# CH3.net
KiCad netlist of a schematic drawn in Altium Designer
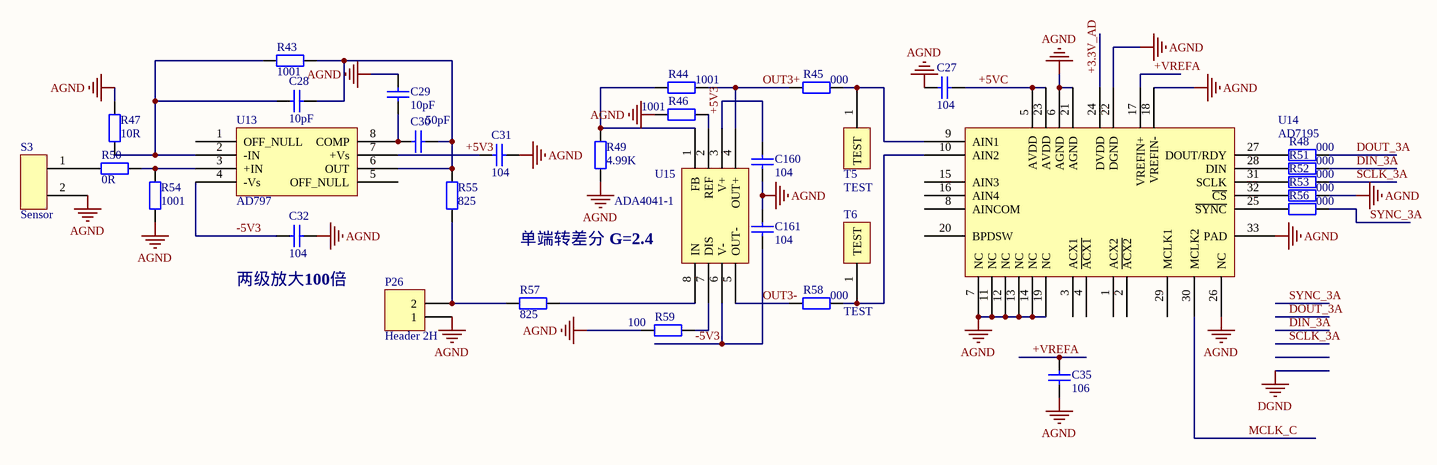
[diagram p0: CH3.SchDoc]

(export (version "E")
  (design (tool "Eeschema 10.0.6"))
  (components
    (comp (ref "C27")
      (value "104")
      (footprint "0805C")
      (description "Capacitor")
      (fields (field (name "PUBLISHER") "Altium Limited"))
      (libsource (lib "Miscellaneous Devices") (part "Cap"))
    )
    (comp (ref "C28")
      (value "10pF")
      (footprint "0603")
      (description "Capacitor")
      (fields (field (name "PUBLISHER") "Altium Limited"))
      (libsource (lib "Miscellaneous Devices") (part "Cap"))
    )
    (comp (ref "C29")
      (value "10pF")
      (footprint "0603")
      (description "Capacitor")
      (fields (field (name "PUBLISHER") "Altium Limited"))
      (libsource (lib "Miscellaneous Devices") (part "Cap"))
    )
    (comp (ref "C30")
      (value "50pF")
      (footprint "0603")
      (description "Capacitor")
      (fields (field (name "PUBLISHER") "Altium Limited"))
      (libsource (lib "Miscellaneous Devices") (part "Cap"))
    )
    (comp (ref "C31")
      (value "104")
      (footprint "0805C")
      (description "Capacitor")
      (fields (field (name "PUBLISHER") "Altium Limited"))
      (libsource (lib "Miscellaneous Devices") (part "Cap"))
    )
    (comp (ref "C32")
      (value "104")
      (footprint "0805C")
      (description "Capacitor")
      (fields (field (name "PUBLISHER") "Altium Limited"))
      (libsource (lib "Miscellaneous Devices") (part "Cap"))
    )
    (comp (ref "C35")
      (value "106")
      (footprint "0603")
      (description "Capacitor")
      (fields (field (name "PUBLISHER") "Altium Limited"))
      (libsource (lib "Miscellaneous Devices") (part "Cap"))
    )
    (comp (ref "C160")
      (value "104")
      (footprint "0805C")
      (description "Capacitor")
      (fields (field (name "PUBLISHER") "Altium Limited"))
      (libsource (lib "Miscellaneous Devices") (part "Cap"))
    )
    (comp (ref "C161")
      (value "104")
      (footprint "0805C")
      (description "Capacitor")
      (fields (field (name "PUBLISHER") "Altium Limited"))
      (libsource (lib "Miscellaneous Devices") (part "Cap"))
    )
    (comp (ref "P26")
      (value "Header 2H")
      (footprint "HDR1X2")
      (description "Header, 2-Pin, Right Angle")
      (fields (field (name "PUBLISHER") "Altium Limited"))
      (libsource (lib "Miscellaneous Connectors") (part "Header 2H"))
    )
    (comp (ref "R43")
      (value "1001")
      (footprint "0603")
      (description "Resistor")
      (fields (field (name "PUBLISHER") "Altium Limited"))
      (libsource (lib "Miscellaneous Devices") (part "Res2"))
    )
    (comp (ref "R44")
      (value "1001")
      (footprint "0603")
      (description "Resistor")
      (fields (field (name "PUBLISHER") "Altium Limited"))
      (libsource (lib "Miscellaneous Devices") (part "Res2"))
    )
    (comp (ref "R45")
      (value "000")
      (footprint "0603")
      (description "Resistor")
      (fields (field (name "PUBLISHER") "Altium Limited"))
      (libsource (lib "Miscellaneous Devices") (part "Res2"))
    )
    (comp (ref "R46")
      (value "1001")
      (footprint "0603")
      (description "Resistor")
      (fields (field (name "PUBLISHER") "Altium Limited"))
      (libsource (lib "Miscellaneous Devices") (part "Res2"))
    )
    (comp (ref "R47")
      (value "10R")
      (footprint "0603")
      (description "Resistor")
      (fields (field (name "PUBLISHER") "Altium Limited"))
      (libsource (lib "") (part "Res2_2"))
    )
    (comp (ref "R48")
      (value "000")
      (footprint "0603")
      (description "Resistor")
      (fields (field (name "PUBLISHER") "Altium Limited"))
      (libsource (lib "Miscellaneous Devices") (part "Res2"))
    )
    (comp (ref "R49")
      (value "4.99K")
      (footprint "0603")
      (description "Resistor")
      (fields (field (name "PUBLISHER") "Altium Limited"))
      (libsource (lib "") (part "Res2_1"))
    )
    (comp (ref "R50")
      (value "0R")
      (footprint "0603")
      (description "Resistor")
      (fields (field (name "PUBLISHER") "Altium Limited"))
      (libsource (lib "Miscellaneous Devices") (part "Res2"))
    )
    (comp (ref "R51")
      (value "000")
      (footprint "0603")
      (description "Resistor")
      (fields (field (name "PUBLISHER") "Altium Limited"))
      (libsource (lib "Miscellaneous Devices") (part "Res2"))
    )
    (comp (ref "R52")
      (value "000")
      (footprint "0603")
      (description "Resistor")
      (fields (field (name "PUBLISHER") "Altium Limited"))
      (libsource (lib "Miscellaneous Devices") (part "Res2"))
    )
    (comp (ref "R53")
      (value "000")
      (footprint "0603")
      (description "Resistor")
      (fields (field (name "PUBLISHER") "Altium Limited"))
      (libsource (lib "Miscellaneous Devices") (part "Res2"))
    )
    (comp (ref "R54")
      (value "1001")
      (footprint "0603")
      (description "Resistor")
      (fields (field (name "PUBLISHER") "Altium Limited"))
      (libsource (lib "") (part "Res2_1"))
    )
    (comp (ref "R55")
      (value "825")
      (footprint "0603")
      (description "Resistor")
      (fields (field (name "PUBLISHER") "Altium Limited"))
      (libsource (lib "") (part "Res2_1"))
    )
    (comp (ref "R56")
      (value "000")
      (footprint "0603")
      (description "Resistor")
      (fields (field (name "PUBLISHER") "Altium Limited"))
      (libsource (lib "Miscellaneous Devices") (part "Res2"))
    )
    (comp (ref "R57")
      (value "825")
      (footprint "0603")
      (description "Resistor")
      (fields (field (name "PUBLISHER") "Altium Limited"))
      (libsource (lib "Miscellaneous Devices") (part "Res2"))
    )
    (comp (ref "R58")
      (value "000")
      (footprint "0603")
      (description "Resistor")
      (fields (field (name "PUBLISHER") "Altium Limited"))
      (libsource (lib "Miscellaneous Devices") (part "Res2"))
    )
    (comp (ref "R59")
      (value "100")
      (footprint "0603")
      (description "Resistor")
      (fields (field (name "PUBLISHER") "Altium Limited"))
      (libsource (lib "Miscellaneous Devices") (part "Res2"))
    )
    (comp (ref "S3") (value "Sensor") (footprint "HDR1X2") (libsource (lib "Schlib1") (part "Sensor")))
    (comp (ref "T5") (value "TEST") (footprint "TEST") (libsource (lib "") (part "TEST_1")))
    (comp (ref "T6") (value "TEST") (footprint "TEST") (libsource (lib "Schlib1") (part "TEST")))
    (comp (ref "U13") (value "AD797") (footprint "SO8") (libsource (lib "Schlib1") (part "AD797")))
    (comp (ref "U14") (value "AD7195") (footprint "VQFN32") (libsource (lib "Schlib1") (part "AD7195")))
    (comp (ref "U15") (value "ADA4041-1") (footprint "SO8") (libsource (lib "Schlib1") (part "ADA4041-1")))
  )
  (nets
    (net (code "1") (name "/+3.3V_AD") (class "Default")
      (node (ref "U14") (pin "24") (pinfunction "DVDD_24") (pintype "passive"))
    )
    (net (code "2") (name "/+5V3") (class "Default")
      (node (ref "C160") (pin "1") (pinfunction "1_1") (pintype "passive"))
      (node (ref "C31") (pin "2") (pinfunction "2_2") (pintype "passive"))
      (node (ref "U13") (pin "7") (pinfunction "+Vs_7") (pintype "passive"))
      (node (ref "U15") (pin "3") (pinfunction "V+_3") (pintype "passive"))
    )
    (net (code "3") (name "/+5VC") (class "Default")
      (node (ref "C27") (pin "2") (pinfunction "2_2") (pintype "passive"))
      (node (ref "U14") (pin "23") (pinfunction "AVDD_23") (pintype "passive"))
      (node (ref "U14") (pin "5") (pinfunction "AVDD_5") (pintype "passive"))
    )
    (net (code "4") (name "/+VREFA") (class "Default")
      (node (ref "C35") (pin "1") (pinfunction "1_1") (pintype "passive"))
      (node (ref "U14") (pin "17") (pinfunction "VREFIN+_17") (pintype "passive"))
    )
    (net (code "5") (name "/-5V3") (class "Default")
      (node (ref "C161") (pin "2") (pinfunction "2_2") (pintype "passive"))
      (node (ref "C32") (pin "2") (pinfunction "2_2") (pintype "passive"))
      (node (ref "R58") (pin "1") (pinfunction "1_1") (pintype "passive"))
      (node (ref "U13") (pin "4") (pinfunction "-Vs_4") (pintype "passive"))
      (node (ref "U15") (pin "5") (pinfunction "OUT-_5") (pintype "passive"))
      (node (ref "U15") (pin "6") (pinfunction "V-_6") (pintype "passive"))
    )
    (net (code "6") (name "/DIN_3A") (class "Default")
      (node (ref "R51") (pin "2") (pinfunction "2_2") (pintype "passive"))
    )
    (net (code "7") (name "/DOUT_3A") (class "Default")
      (node (ref "R48") (pin "2") (pinfunction "2_2") (pintype "passive"))
    )
    (net (code "8") (name "/MCLK_C") (class "Default")
      (node (ref "U14") (pin "30") (pinfunction "MCLK2_30") (pintype "passive"))
    )
    (net (code "9") (name "/OUT3+") (class "Default")
      (node (ref "R44") (pin "2") (pinfunction "2_2") (pintype "passive"))
      (node (ref "R45") (pin "1") (pinfunction "1_1") (pintype "passive"))
      (node (ref "U15") (pin "4") (pinfunction "OUT+_4") (pintype "passive"))
    )
    (net (code "10") (name "/SCLK_3A") (class "Default")
      (node (ref "R52") (pin "2") (pinfunction "2_2") (pintype "passive"))
    )
    (net (code "11") (name "/SYNC_3A") (class "Default")
      (node (ref "R56") (pin "2") (pinfunction "2_2") (pintype "passive"))
    )
    (net (code "12") (name "AGND") (class "Default")
      (node (ref "C160") (pin "2") (pinfunction "2_2") (pintype "passive"))
      (node (ref "C161") (pin "1") (pinfunction "1_1") (pintype "passive"))
      (node (ref "C27") (pin "1") (pinfunction "1_1") (pintype "passive"))
      (node (ref "C29") (pin "2") (pinfunction "2_2") (pintype "passive"))
      (node (ref "C31") (pin "1") (pinfunction "1_1") (pintype "passive"))
      (node (ref "C32") (pin "1") (pinfunction "1_1") (pintype "passive"))
      (node (ref "C35") (pin "2") (pinfunction "2_2") (pintype "passive"))
      (node (ref "P26") (pin "1") (pinfunction "1_1") (pintype "passive"))
      (node (ref "R46") (pin "1") (pinfunction "1_1") (pintype "passive"))
      (node (ref "R47") (pin "1") (pinfunction "1_1") (pintype "passive"))
      (node (ref "R49") (pin "1") (pinfunction "1_1") (pintype "passive"))
      (node (ref "R53") (pin "2") (pinfunction "2_2") (pintype "passive"))
      (node (ref "R54") (pin "1") (pinfunction "1_1") (pintype "passive"))
      (node (ref "R59") (pin "1") (pinfunction "1_1") (pintype "passive"))
      (node (ref "S3") (pin "2") (pinfunction "2_2") (pintype "passive"))
      (node (ref "U14") (pin "11") (pinfunction "NC_11") (pintype "passive"))
      (node (ref "U14") (pin "12") (pinfunction "NC_12") (pintype "passive"))
      (node (ref "U14") (pin "13") (pinfunction "NC_13") (pintype "passive"))
      (node (ref "U14") (pin "14") (pinfunction "NC_14") (pintype "passive"))
      (node (ref "U14") (pin "18") (pinfunction "VREFIN-_18") (pintype "passive"))
      (node (ref "U14") (pin "19") (pinfunction "NC_19") (pintype "passive"))
      (node (ref "U14") (pin "21") (pinfunction "AGND_21") (pintype "passive"))
      (node (ref "U14") (pin "22") (pinfunction "DGND_22") (pintype "passive"))
      (node (ref "U14") (pin "26") (pinfunction "NC_26") (pintype "passive"))
      (node (ref "U14") (pin "33") (pinfunction "PAD_33") (pintype "passive"))
      (node (ref "U14") (pin "6") (pinfunction "AGND_6") (pintype "passive"))
      (node (ref "U14") (pin "7") (pinfunction "NC_7") (pintype "passive"))
    )
    (net (code "14") (name "Net-(P26-Pad2)") (class "Default")
      (node (ref "P26") (pin "2") (pinfunction "2_2") (pintype "passive"))
      (node (ref "R55") (pin "1") (pinfunction "1_1") (pintype "passive"))
      (node (ref "R57") (pin "1") (pinfunction "1_1") (pintype "passive"))
    )
    (net (code "15") (name "Net-(R50-Pad1)") (class "Default")
      (node (ref "R50") (pin "1") (pinfunction "1_1") (pintype "passive"))
      (node (ref "S3") (pin "1") (pinfunction "1_1") (pintype "passive"))
    )
    (net (code "16") (name "Net-(T5-TEST)") (class "Default")
      (node (ref "R45") (pin "2") (pinfunction "2_2") (pintype "passive"))
      (node (ref "T5") (pin "1") (pinfunction "TEST_1") (pintype "passive"))
      (node (ref "U14") (pin "9") (pinfunction "AIN1_9") (pintype "passive"))
    )
    (net (code "17") (name "Net-(T6-TEST)") (class "Default")
      (node (ref "R58") (pin "2") (pinfunction "2_2") (pintype "passive"))
      (node (ref "T6") (pin "1") (pinfunction "TEST_1") (pintype "passive"))
      (node (ref "U14") (pin "10") (pinfunction "AIN2_10") (pintype "passive"))
    )
    (net (code "18") (name "Net-(U13-+IN)") (class "Default")
      (node (ref "R50") (pin "2") (pinfunction "2_2") (pintype "passive"))
      (node (ref "R54") (pin "2") (pinfunction "2_2") (pintype "passive"))
      (node (ref "U13") (pin "3") (pinfunction "+IN_3") (pintype "passive"))
    )
    (net (code "19") (name "Net-(U13--IN)") (class "Default")
      (node (ref "C28") (pin "2") (pinfunction "2_2") (pintype "passive"))
      (node (ref "R43") (pin "1") (pinfunction "1_1") (pintype "passive"))
      (node (ref "R47") (pin "2") (pinfunction "2_2") (pintype "passive"))
      (node (ref "U13") (pin "2") (pinfunction "-IN_2") (pintype "passive"))
    )
    (net (code "20") (name "Net-(U13-COMP)") (class "Default")
      (node (ref "C29") (pin "1") (pinfunction "1_1") (pintype "passive"))
      (node (ref "C30") (pin "2") (pinfunction "2_2") (pintype "passive"))
      (node (ref "U13") (pin "8") (pinfunction "COMP_8") (pintype "passive"))
    )
    (net (code "21") (name "Net-(U13-OUT)") (class "Default")
      (node (ref "C28") (pin "1") (pinfunction "1_1") (pintype "passive"))
      (node (ref "C30") (pin "1") (pinfunction "1_1") (pintype "passive"))
      (node (ref "R43") (pin "2") (pinfunction "2_2") (pintype "passive"))
      (node (ref "R55") (pin "2") (pinfunction "2_2") (pintype "passive"))
      (node (ref "U13") (pin "6") (pinfunction "OUT_6") (pintype "passive"))
    )
    (net (code "22") (name "Net-(U14-DIN)") (class "Default")
      (node (ref "R51") (pin "1") (pinfunction "1_1") (pintype "passive"))
      (node (ref "U14") (pin "28") (pinfunction "DIN_28") (pintype "passive"))
    )
    (net (code "23") (name "Net-(U14-DOUT{slash}RDY)") (class "Default")
      (node (ref "R48") (pin "1") (pinfunction "1_1") (pintype "passive"))
      (node (ref "U14") (pin "27") (pinfunction "DOUT/RDY_27") (pintype "passive"))
    )
    (net (code "24") (name "Net-(U14-SCLK)") (class "Default")
      (node (ref "R52") (pin "1") (pinfunction "1_1") (pintype "passive"))
      (node (ref "U14") (pin "31") (pinfunction "SCLK_31") (pintype "passive"))
    )
    (net (code "25") (name "Net-(U14-~{CS})") (class "Default")
      (node (ref "R53") (pin "1") (pinfunction "1_1") (pintype "passive"))
      (node (ref "U14") (pin "32") (pinfunction "~{CS}_32") (pintype "passive"))
    )
    (net (code "26") (name "Net-(U14-~{SYNC})") (class "Default")
      (node (ref "R56") (pin "1") (pinfunction "1_1") (pintype "passive"))
      (node (ref "U14") (pin "25") (pinfunction "~{SYNC}_25") (pintype "passive"))
    )
    (net (code "27") (name "Net-(U15-DIS)") (class "Default")
      (node (ref "R59") (pin "2") (pinfunction "2_2") (pintype "passive"))
      (node (ref "U15") (pin "7") (pinfunction "DIS_7") (pintype "passive"))
    )
    (net (code "28") (name "Net-(U15-FB)") (class "Default")
      (node (ref "R44") (pin "1") (pinfunction "1_1") (pintype "passive"))
      (node (ref "R49") (pin "2") (pinfunction "2_2") (pintype "passive"))
      (node (ref "U15") (pin "1") (pinfunction "FB_1") (pintype "passive"))
    )
    (net (code "29") (name "Net-(U15-IN)") (class "Default")
      (node (ref "R57") (pin "2") (pinfunction "2_2") (pintype "passive"))
      (node (ref "U15") (pin "8") (pinfunction "IN_8") (pintype "passive"))
    )
    (net (code "30") (name "Net-(U15-REF)") (class "Default")
      (node (ref "R46") (pin "2") (pinfunction "2_2") (pintype "passive"))
      (node (ref "U15") (pin "2") (pinfunction "REF_2") (pintype "passive"))
    )
    (net (code "31") (name "unconnected-(U13-OFF_NULL-Pad1)") (class "Default")
      (node (ref "U13") (pin "1") (pinfunction "OFF_NULL_1") (pintype "passive"))
    )
    (net (code "32") (name "unconnected-(U13-OFF_NULL-Pad5)") (class "Default")
      (node (ref "U13") (pin "5") (pinfunction "OFF_NULL_5") (pintype "passive"))
    )
    (net (code "33") (name "unconnected-(U14-ACX1-Pad3)") (class "Default")
      (node (ref "U14") (pin "3") (pinfunction "ACX1_3") (pintype "passive"))
    )
    (net (code "34") (name "unconnected-(U14-ACX2-Pad1)") (class "Default")
      (node (ref "U14") (pin "1") (pinfunction "ACX2_1") (pintype "passive"))
    )
    (net (code "35") (name "unconnected-(U14-AIN3-Pad15)") (class "Default")
      (node (ref "U14") (pin "15") (pinfunction "AIN3_15") (pintype "passive"))
    )
    (net (code "36") (name "unconnected-(U14-AIN4-Pad16)") (class "Default")
      (node (ref "U14") (pin "16") (pinfunction "AIN4_16") (pintype "passive"))
    )
    (net (code "37") (name "unconnected-(U14-AINCOM-Pad8)") (class "Default")
      (node (ref "U14") (pin "8") (pinfunction "AINCOM_8") (pintype "passive"))
    )
    (net (code "38") (name "unconnected-(U14-BPDSW-Pad20)") (class "Default")
      (node (ref "U14") (pin "20") (pinfunction "BPDSW_20") (pintype "passive"))
    )
    (net (code "39") (name "unconnected-(U14-MCLK1-Pad29)") (class "Default")
      (node (ref "U14") (pin "29") (pinfunction "MCLK1_29") (pintype "passive"))
    )
    (net (code "40") (name "unconnected-(U14-~{ACX1}-Pad4)") (class "Default")
      (node (ref "U14") (pin "4") (pinfunction "~{ACX1}_4") (pintype "passive"))
    )
    (net (code "41") (name "unconnected-(U14-~{ACX2}-Pad2)") (class "Default")
      (node (ref "U14") (pin "2") (pinfunction "~{ACX2}_2") (pintype "passive"))
    )
  )
)
